# V_9.net
KiCad netlist of a schematic drawn in Altium Designer
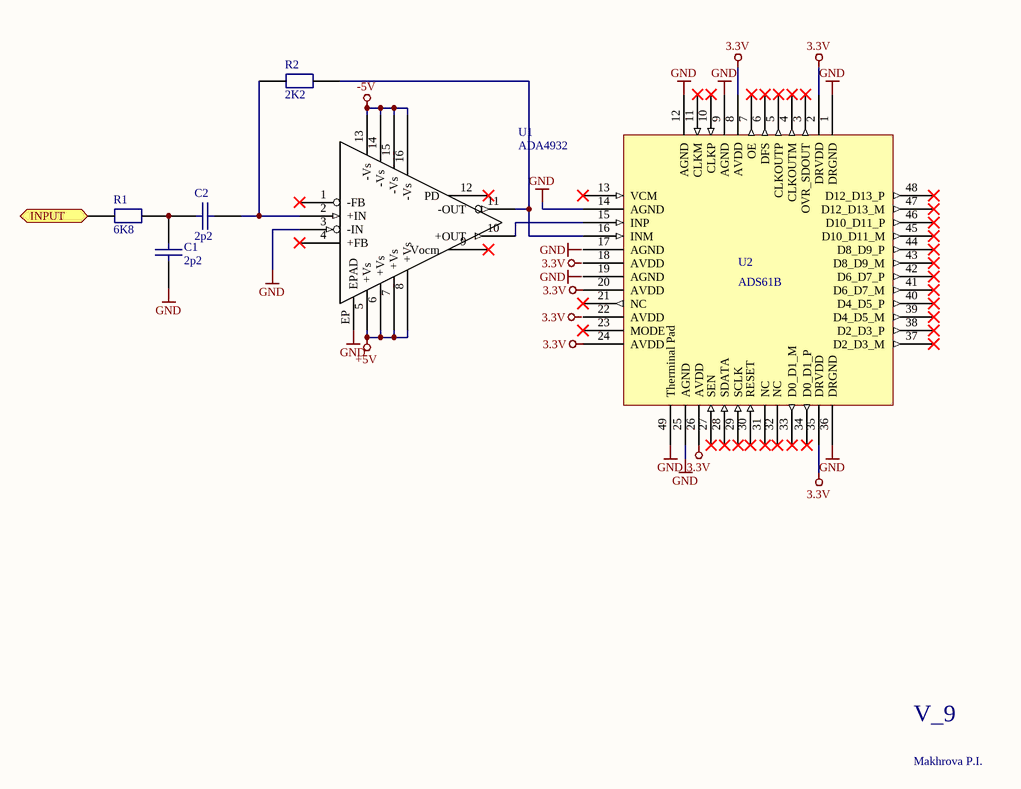
[diagram p0: V_9.SchDoc]

(export (version "E")
  (design (tool "Eeschema 10.0.6"))
  (components
    (comp (ref "C1") (value "2p2") (footprint "Cap0805") (libsource (lib "V_1") (part "Cap")))
    (comp (ref "C2") (value "2p2") (footprint "Cap0805") (libsource (lib "V_1") (part "Cap")))
    (comp (ref "R1") (value "6K8") (footprint "Res0805") (libsource (lib "V_1") (part "Res")))
    (comp (ref "R2") (value "2K2") (footprint "Res0805") (libsource (lib "V_1") (part "Res")))
    (comp (ref "U1") (value "ADA4932") (footprint "ADA4922") (libsource (lib "V_9") (part "ADA4932")))
    (comp (ref "U2") (value "ADS61B") (footprint "ADS61B49") (libsource (lib "V_1") (part "ADS61B49")))
  )
  (nets
    (net (code "1") (name "+5V") (class "Default")
      (node (ref "U1") (pin "5") (pinfunction "+Vs_5") (pintype "power_in"))
      (node (ref "U1") (pin "6") (pinfunction "+Vs_6") (pintype "power_in"))
      (node (ref "U1") (pin "7") (pinfunction "+Vs_7") (pintype "power_in"))
      (node (ref "U1") (pin "8") (pinfunction "+Vs_8") (pintype "power_in"))
    )
    (net (code "2") (name "-5V") (class "Default")
      (node (ref "U1") (pin "13") (pinfunction "-Vs_13") (pintype "power_in"))
      (node (ref "U1") (pin "14") (pinfunction "-Vs_14") (pintype "power_in"))
      (node (ref "U1") (pin "15") (pinfunction "-Vs_15") (pintype "power_in"))
      (node (ref "U1") (pin "16") (pinfunction "-Vs_16") (pintype "power_in"))
    )
    (net (code "3") (name "/INPUT") (class "Default")
      (node (ref "R1") (pin "1") (pinfunction "1_1") (pintype "passive"))
    )
    (net (code "4") (name "3.3V") (class "Default")
      (node (ref "U2") (pin "2") (pinfunction "DRVDD_2") (pintype "power_in"))
      (node (ref "U2") (pin "20") (pinfunction "AVDD_20") (pintype "power_in"))
      (node (ref "U2") (pin "24") (pinfunction "AVDD_24") (pintype "power_in"))
      (node (ref "U2") (pin "26") (pinfunction "AVDD_26") (pintype "power_in"))
      (node (ref "U2") (pin "35") (pinfunction "DRVDD_35") (pintype "power_in"))
      (node (ref "U2") (pin "8") (pinfunction "AVDD_8") (pintype "power_in"))
    )
    (net (code "5") (name "GND") (class "Default")
      (node (ref "C1") (pin "1") (pinfunction "1_1") (pintype "passive"))
      (node (ref "U1") (pin "3") (pinfunction "-IN_3") (pintype "input"))
      (node (ref "U1") (pin "EP") (pinfunction "EPAD_EP") (pintype "power_in"))
      (node (ref "U2") (pin "1") (pinfunction "DRGND_1") (pintype "power_in"))
      (node (ref "U2") (pin "12") (pinfunction "AGND_12") (pintype "power_in"))
      (node (ref "U2") (pin "14") (pinfunction "AGND_14") (pintype "power_in"))
      (node (ref "U2") (pin "25") (pinfunction "AGND_25") (pintype "power_in"))
      (node (ref "U2") (pin "36") (pinfunction "DRGND_36") (pintype "power_in"))
      (node (ref "U2") (pin "49") (pinfunction "Therminal_Pad_49") (pintype "power_in"))
      (node (ref "U2") (pin "9") (pinfunction "AGND_9") (pintype "power_in"))
    )
    (net (code "6") (name "Net-(C1-Pad2)") (class "Default")
      (node (ref "C1") (pin "2") (pinfunction "2_2") (pintype "passive"))
      (node (ref "C2") (pin "2") (pinfunction "2_2") (pintype "passive"))
      (node (ref "R1") (pin "2") (pinfunction "2_2") (pintype "passive"))
    )
    (net (code "7") (name "Net-(U1-+IN)") (class "Default")
      (node (ref "C2") (pin "1") (pinfunction "1_1") (pintype "passive"))
      (node (ref "R2") (pin "1") (pinfunction "1_1") (pintype "passive"))
      (node (ref "U1") (pin "2") (pinfunction "+IN_2") (pintype "input"))
    )
    (net (code "8") (name "Net-(U1-+OUT)") (class "Default")
      (node (ref "U1") (pin "10") (pinfunction "+OUT_10") (pintype "output"))
      (node (ref "U2") (pin "15") (pinfunction "INP_15") (pintype "input"))
    )
    (net (code "9") (name "Net-(U1--OUT)") (class "Default")
      (node (ref "R2") (pin "2") (pinfunction "2_2") (pintype "passive"))
      (node (ref "U1") (pin "11") (pinfunction "-OUT_11") (pintype "output"))
      (node (ref "U2") (pin "16") (pinfunction "INM_16") (pintype "input"))
    )
    (net (code "10") (name "unconnected-(U1-+FB-Pad4)") (class "Default")
      (node (ref "U1") (pin "4") (pinfunction "+FB_4") (pintype "passive+no_connect"))
    )
    (net (code "11") (name "unconnected-(U1--FB-Pad1)") (class "Default")
      (node (ref "U1") (pin "1") (pinfunction "-FB_1") (pintype "passive+no_connect"))
    )
    (net (code "12") (name "unconnected-(U1-PD-Pad12)") (class "Default")
      (node (ref "U1") (pin "12") (pinfunction "PD_12") (pintype "passive+no_connect"))
    )
    (net (code "13") (name "unconnected-(U1-Vocm-Pad9)") (class "Default")
      (node (ref "U1") (pin "9") (pinfunction "Vocm_9") (pintype "power_in+no_connect"))
    )
    (net (code "14") (name "unconnected-(U2-AGND-Pad17)") (class "Default")
      (node (ref "U2") (pin "17") (pinfunction "AGND_17") (pintype "power_in"))
    )
    (net (code "15") (name "unconnected-(U2-AGND-Pad19)") (class "Default")
      (node (ref "U2") (pin "19") (pinfunction "AGND_19") (pintype "power_in"))
    )
    (net (code "16") (name "unconnected-(U2-AVDD-Pad18)") (class "Default")
      (node (ref "U2") (pin "18") (pinfunction "AVDD_18") (pintype "power_in"))
    )
    (net (code "17") (name "unconnected-(U2-AVDD-Pad22)") (class "Default")
      (node (ref "U2") (pin "22") (pinfunction "AVDD_22") (pintype "power_in"))
    )
    (net (code "18") (name "unconnected-(U2-CLKM-Pad11)") (class "Default")
      (node (ref "U2") (pin "11") (pinfunction "CLKM_11") (pintype "input+no_connect"))
    )
    (net (code "19") (name "unconnected-(U2-CLKOUTM-Pad4)") (class "Default")
      (node (ref "U2") (pin "4") (pinfunction "CLKOUTM_4") (pintype "output+no_connect"))
    )
    (net (code "20") (name "unconnected-(U2-CLKOUTP-Pad5)") (class "Default")
      (node (ref "U2") (pin "5") (pinfunction "CLKOUTP_5") (pintype "output+no_connect"))
    )
    (net (code "21") (name "unconnected-(U2-CLKP-Pad10)") (class "Default")
      (node (ref "U2") (pin "10") (pinfunction "CLKP_10") (pintype "input+no_connect"))
    )
    (net (code "22") (name "unconnected-(U2-D0_D1_M-Pad33)") (class "Default")
      (node (ref "U2") (pin "33") (pinfunction "D0_D1_M_33") (pintype "output+no_connect"))
    )
    (net (code "23") (name "unconnected-(U2-D0_D1_P-Pad34)") (class "Default")
      (node (ref "U2") (pin "34") (pinfunction "D0_D1_P_34") (pintype "output+no_connect"))
    )
    (net (code "24") (name "unconnected-(U2-D2_D3_M-Pad37)") (class "Default")
      (node (ref "U2") (pin "37") (pinfunction "D2_D3_M_37") (pintype "output+no_connect"))
    )
    (net (code "25") (name "unconnected-(U2-D2_D3_P-Pad38)") (class "Default")
      (node (ref "U2") (pin "38") (pinfunction "D2_D3_P_38") (pintype "output+no_connect"))
    )
    (net (code "26") (name "unconnected-(U2-D4_D5_M-Pad39)") (class "Default")
      (node (ref "U2") (pin "39") (pinfunction "D4_D5_M_39") (pintype "output+no_connect"))
    )
    (net (code "27") (name "unconnected-(U2-D4_D5_P-Pad40)") (class "Default")
      (node (ref "U2") (pin "40") (pinfunction "D4_D5_P_40") (pintype "output+no_connect"))
    )
    (net (code "28") (name "unconnected-(U2-D6_D7_M-Pad41)") (class "Default")
      (node (ref "U2") (pin "41") (pinfunction "D6_D7_M_41") (pintype "output+no_connect"))
    )
    (net (code "29") (name "unconnected-(U2-D6_D7_P-Pad42)") (class "Default")
      (node (ref "U2") (pin "42") (pinfunction "D6_D7_P_42") (pintype "output+no_connect"))
    )
    (net (code "30") (name "unconnected-(U2-D8_D9_M-Pad43)") (class "Default")
      (node (ref "U2") (pin "43") (pinfunction "D8_D9_M_43") (pintype "output+no_connect"))
    )
    (net (code "31") (name "unconnected-(U2-D8_D9_P-Pad44)") (class "Default")
      (node (ref "U2") (pin "44") (pinfunction "D8_D9_P_44") (pintype "output+no_connect"))
    )
    (net (code "32") (name "unconnected-(U2-D10_D11_M-Pad45)") (class "Default")
      (node (ref "U2") (pin "45") (pinfunction "D10_D11_M_45") (pintype "output+no_connect"))
    )
    (net (code "33") (name "unconnected-(U2-D10_D11_P-Pad46)") (class "Default")
      (node (ref "U2") (pin "46") (pinfunction "D10_D11_P_46") (pintype "output+no_connect"))
    )
    (net (code "34") (name "unconnected-(U2-D12_D13_M-Pad47)") (class "Default")
      (node (ref "U2") (pin "47") (pinfunction "D12_D13_M_47") (pintype "output+no_connect"))
    )
    (net (code "35") (name "unconnected-(U2-D12_D13_P-Pad48)") (class "Default")
      (node (ref "U2") (pin "48") (pinfunction "D12_D13_P_48") (pintype "output+no_connect"))
    )
    (net (code "36") (name "unconnected-(U2-DFS-Pad6)") (class "Default")
      (node (ref "U2") (pin "6") (pinfunction "DFS_6") (pintype "output+no_connect"))
    )
    (net (code "37") (name "unconnected-(U2-MODE-Pad23)") (class "Default")
      (node (ref "U2") (pin "23") (pinfunction "MODE_23") (pintype "passive+no_connect"))
    )
    (net (code "38") (name "unconnected-(U2-NC-Pad21)") (class "Default")
      (node (ref "U2") (pin "21") (pinfunction "NC_21") (pintype "output+no_connect"))
    )
    (net (code "39") (name "unconnected-(U2-NC-Pad31)") (class "Default")
      (node (ref "U2") (pin "31") (pinfunction "NC_31") (pintype "passive+no_connect"))
    )
    (net (code "40") (name "unconnected-(U2-NC-Pad32)") (class "Default")
      (node (ref "U2") (pin "32") (pinfunction "NC_32") (pintype "passive+no_connect"))
    )
    (net (code "41") (name "unconnected-(U2-OE-Pad7)") (class "Default")
      (node (ref "U2") (pin "7") (pinfunction "OE_7") (pintype "output+no_connect"))
    )
    (net (code "42") (name "unconnected-(U2-OVR_SDOUT-Pad3)") (class "Default")
      (node (ref "U2") (pin "3") (pinfunction "OVR_SDOUT_3") (pintype "output+no_connect"))
    )
    (net (code "43") (name "unconnected-(U2-RESET-Pad30)") (class "Default")
      (node (ref "U2") (pin "30") (pinfunction "RESET_30") (pintype "input+no_connect"))
    )
    (net (code "44") (name "unconnected-(U2-SCLK-Pad29)") (class "Default")
      (node (ref "U2") (pin "29") (pinfunction "SCLK_29") (pintype "input+no_connect"))
    )
    (net (code "45") (name "unconnected-(U2-SDATA-Pad28)") (class "Default")
      (node (ref "U2") (pin "28") (pinfunction "SDATA_28") (pintype "input+no_connect"))
    )
    (net (code "46") (name "unconnected-(U2-SEN-Pad27)") (class "Default")
      (node (ref "U2") (pin "27") (pinfunction "SEN_27") (pintype "input+no_connect"))
    )
    (net (code "47") (name "unconnected-(U2-VCM-Pad13)") (class "Default")
      (node (ref "U2") (pin "13") (pinfunction "VCM_13") (pintype "input+no_connect"))
    )
  )
)
